# r3.net
KiCad netlist of a schematic drawn in EasyEDA
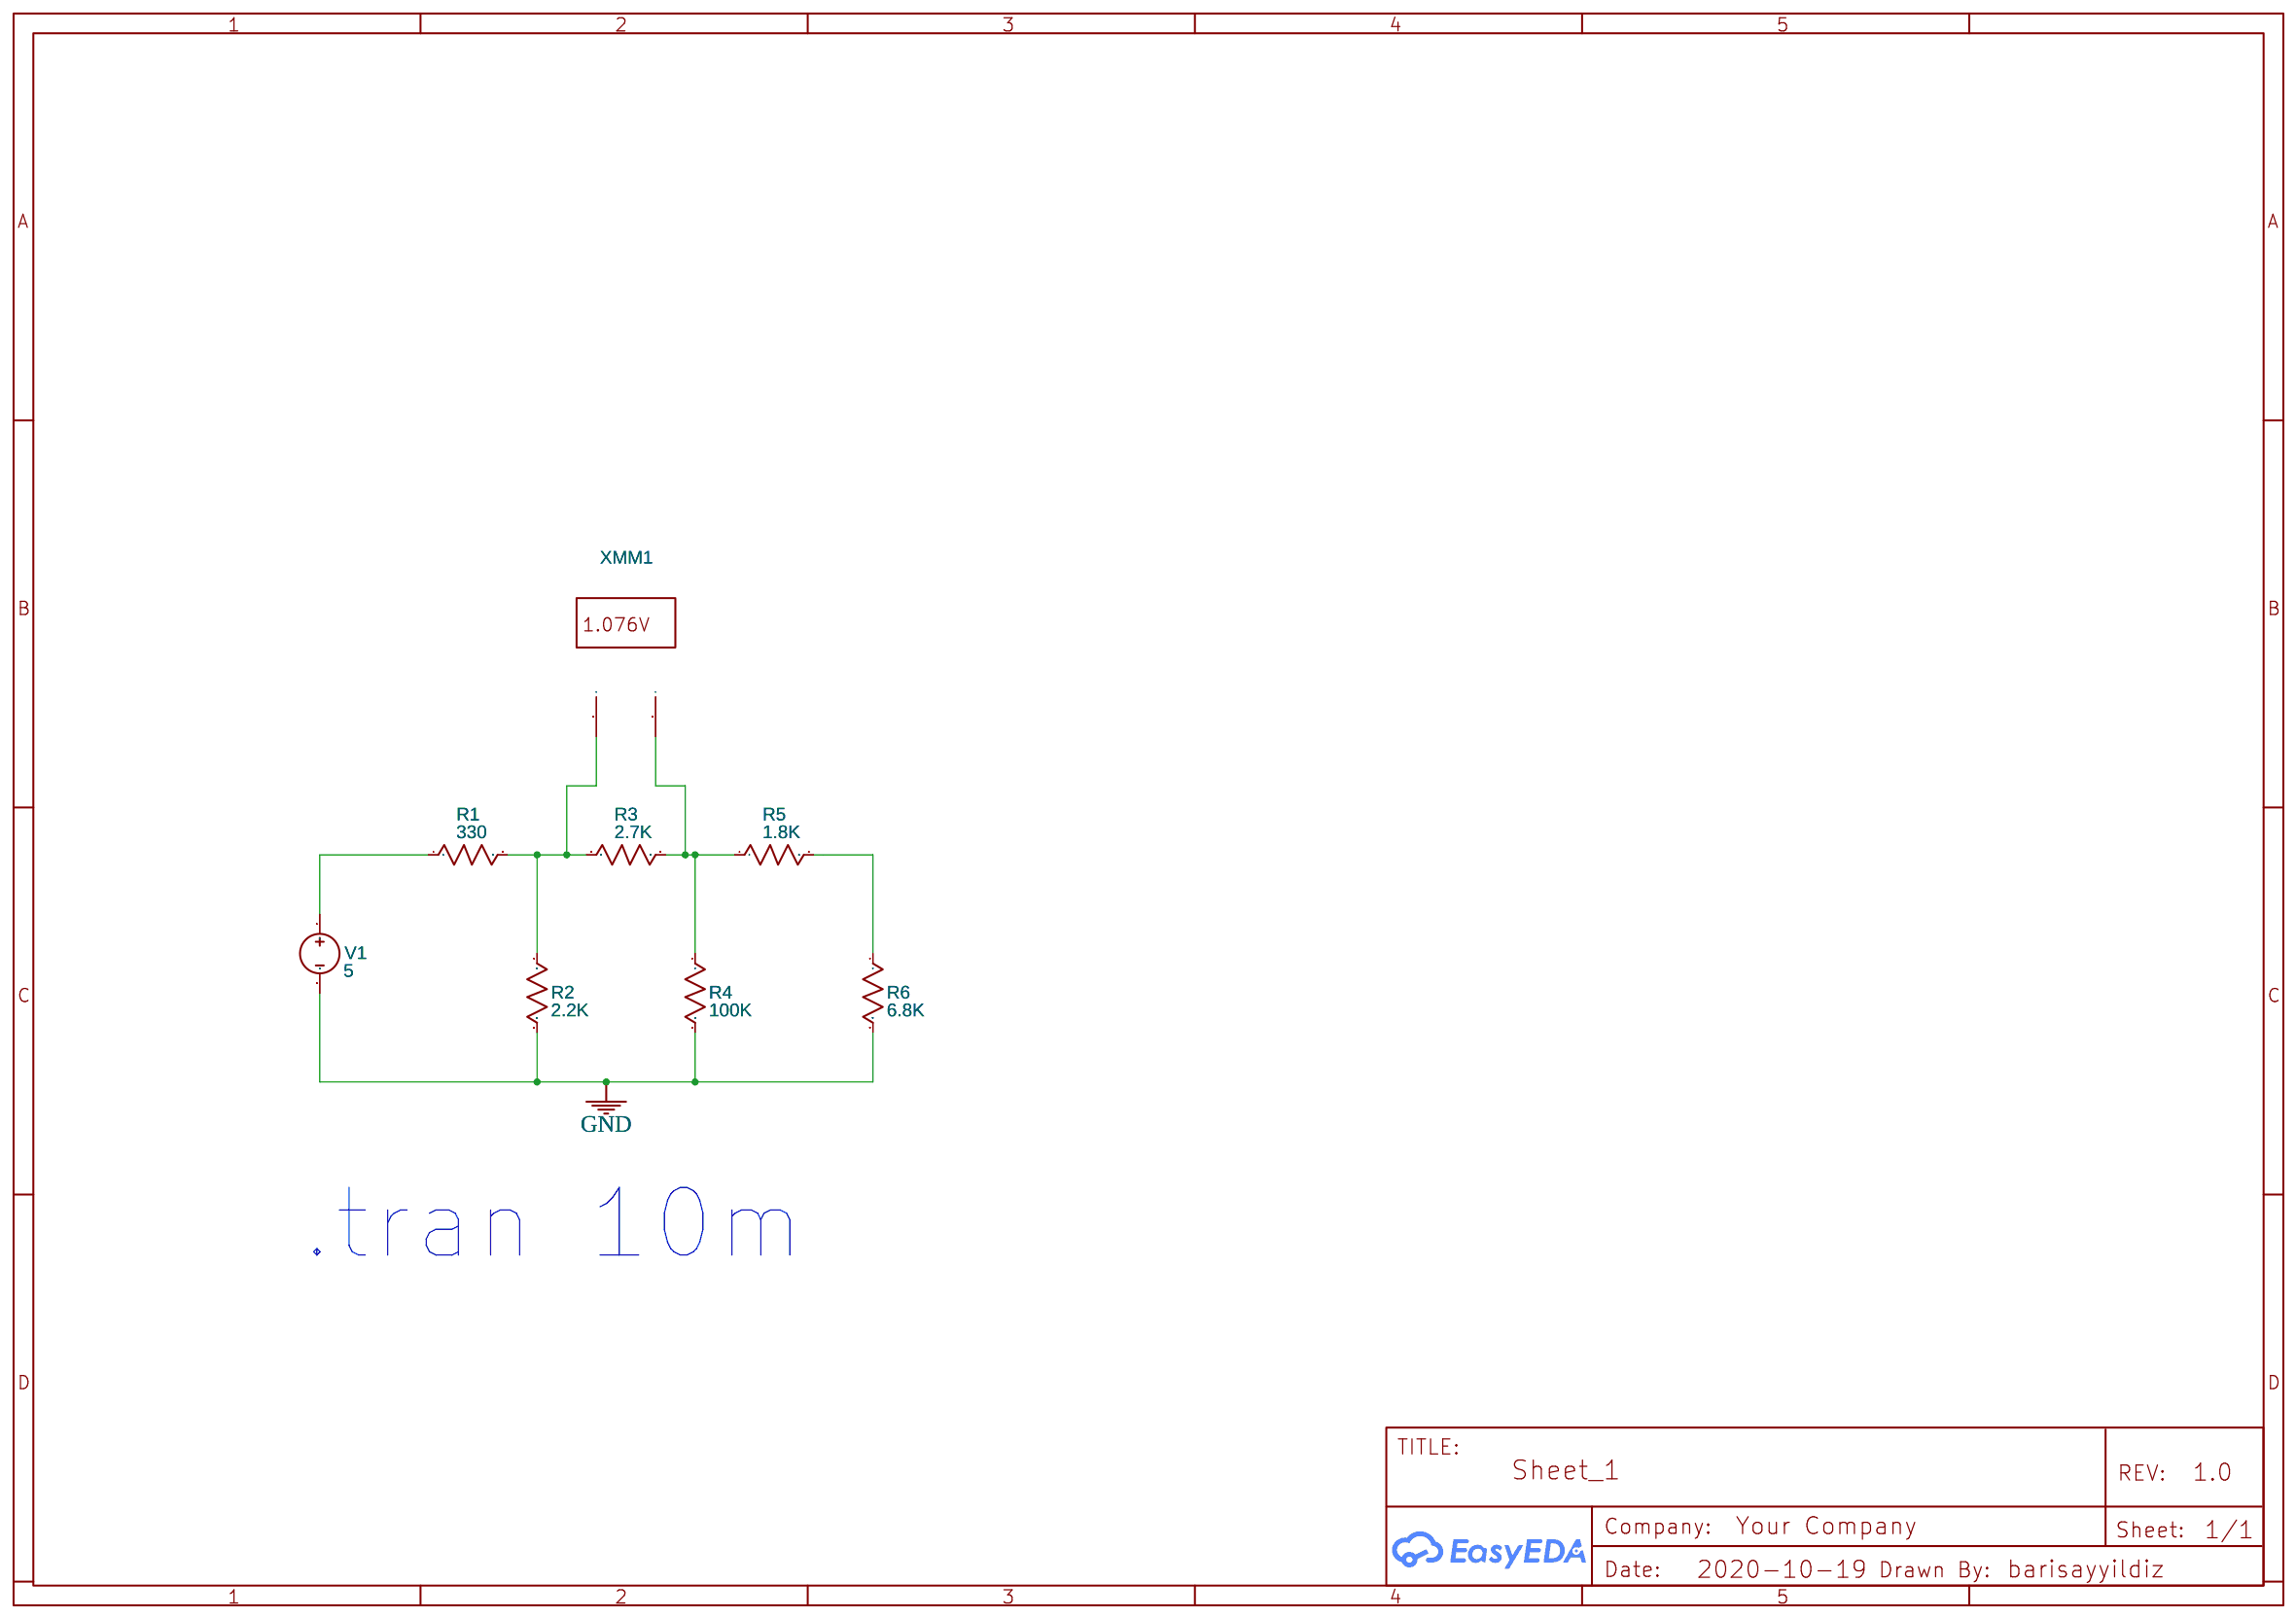
[diagram p0: schematic sheet]

(export (version "E")
  (design (tool "Eeschema 10.0.6"))
  (components
    (comp (ref "R1") (value "330") (libsource (lib "") (part "Resistor_US_1")))
    (comp (ref "R2") (value "2.2K") (libsource (lib "") (part "Resistor_US")))
    (comp (ref "R3") (value "2.7K") (libsource (lib "") (part "Resistor_US_1")))
    (comp (ref "R4") (value "100K") (libsource (lib "") (part "Resistor_US")))
    (comp (ref "R5") (value "1.8K") (libsource (lib "") (part "Resistor_US_1")))
    (comp (ref "R6") (value "6.8K") (libsource (lib "") (part "Resistor_US")))
    (comp (ref "V1") (value "5") (libsource (lib "") (part "VDC")))
    (comp (ref "XMM1") (value "Multimeter") (libsource (lib "") (part "MULTIMETER")))
  )
  (nets
    (net (code "1") (name "GND") (class "Default")
      (node (ref "R2") (pin "2") (pinfunction "2_2") (pintype "unspecified"))
      (node (ref "R4") (pin "2") (pinfunction "2_2") (pintype "unspecified"))
      (node (ref "R6") (pin "2") (pinfunction "2_2") (pintype "unspecified"))
      (node (ref "V1") (pin "2") (pinfunction "2_2") (pintype "unspecified"))
    )
    (net (code "2") (name "Net-(R1-Pad1)") (class "Default")
      (node (ref "R1") (pin "1") (pinfunction "1_1") (pintype "unspecified"))
      (node (ref "V1") (pin "1") (pinfunction "1_1") (pintype "unspecified"))
    )
    (net (code "3") (name "Net-(R5-Pad2)") (class "Default")
      (node (ref "R5") (pin "2") (pinfunction "2_2") (pintype "unspecified"))
      (node (ref "R6") (pin "1") (pinfunction "1_1") (pintype "unspecified"))
    )
    (net (code "4") (name "Net-(XMM1-+)") (class "Default")
      (node (ref "R1") (pin "2") (pinfunction "2_2") (pintype "unspecified"))
      (node (ref "R2") (pin "1") (pinfunction "1_1") (pintype "unspecified"))
      (node (ref "R3") (pin "1") (pinfunction "1_1") (pintype "unspecified"))
      (node (ref "XMM1") (pin "1") (pinfunction "+_1") (pintype "unspecified"))
    )
    (net (code "5") (name "Net-(XMM1-I)") (class "Default")
      (node (ref "R3") (pin "2") (pinfunction "2_2") (pintype "unspecified"))
      (node (ref "R4") (pin "1") (pinfunction "1_1") (pintype "unspecified"))
      (node (ref "R5") (pin "1") (pinfunction "1_1") (pintype "unspecified"))
      (node (ref "XMM1") (pin "2") (pinfunction "I_2") (pintype "unspecified"))
    )
  )
)
